# OLED.net
KiCad netlist of a schematic drawn in Altium Designer
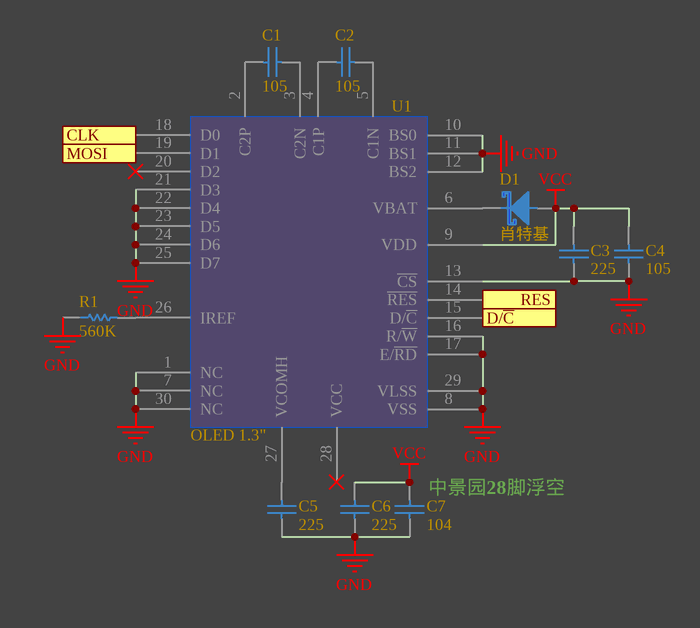
[diagram p0: OLED.SchDoc]

(export (version "E")
  (design (tool "Eeschema 10.0.6"))
  (components
    (comp (ref "C1")
      (value "105")
      (footprint "C0603")
      (description "Capacitor")
      (fields (field (name "PUBLISHER") "Altium Limited"))
      (libsource (lib "iMag") (part "电容"))
    )
    (comp (ref "C2")
      (value "105")
      (footprint "C0603")
      (description "Capacitor")
      (fields (field (name "PUBLISHER") "Altium Limited"))
      (libsource (lib "iMag") (part "电容"))
    )
    (comp (ref "C3")
      (value "225")
      (footprint "C0603")
      (description "Capacitor")
      (fields (field (name "PUBLISHER") "Altium Limited"))
      (libsource (lib "iMag") (part "电容"))
    )
    (comp (ref "C4")
      (value "105")
      (footprint "C0603")
      (description "Capacitor")
      (fields (field (name "PUBLISHER") "Altium Limited"))
      (libsource (lib "iMag") (part "电容"))
    )
    (comp (ref "C5")
      (value "225")
      (footprint "C0603")
      (description "Capacitor")
      (fields (field (name "PUBLISHER") "Altium Limited"))
      (libsource (lib "iMag") (part "电容"))
    )
    (comp (ref "C6")
      (value "225")
      (footprint "C0603")
      (description "Capacitor")
      (fields (field (name "PUBLISHER") "Altium Limited"))
      (libsource (lib "iMag") (part "电容"))
    )
    (comp (ref "C7")
      (value "104")
      (footprint "C0402")
      (description "Capacitor")
      (fields (field (name "PUBLISHER") "Altium Limited"))
      (libsource (lib "iMag") (part "电容"))
    )
    (comp (ref "D1")
      (value "肖特基")
      (footprint "SOD-123")
      (description "Schottky Diode")
      (libsource (lib "iMag") (part "肖特基"))
    )
    (comp (ref "R1")
      (value "560K")
      (footprint "R0402")
      (description "Resistor")
      (fields (field (name "PUBLISHER") "Altium Limited"))
      (libsource (lib "iMag") (part "电阻"))
    )
    (comp (ref "U1")
      (value "OLED 1.3\"")
      (footprint "OLED1.3\"")
      (description "SSD1306")
      (libsource (lib "iMag") (part "SSD1315"))
    )
  )
  (nets
    (net (code "1") (name "/CLK") (class "Default")
      (node (ref "U1") (pin "18") (pinfunction "D0_18") (pintype "passive"))
    )
    (net (code "2") (name "/D{slash}~{C}") (class "Default")
      (node (ref "U1") (pin "15") (pinfunction "D/~{C}_15") (pintype "passive"))
    )
    (net (code "3") (name "/MOSI") (class "Default")
      (node (ref "U1") (pin "19") (pinfunction "D1_19") (pintype "passive"))
    )
    (net (code "4") (name "/RES") (class "Default")
      (node (ref "U1") (pin "14") (pinfunction "RES_14") (pintype "passive"))
    )
    (net (code "5") (name "GND") (class "Default")
      (node (ref "C3") (pin "1") (pinfunction "1_1") (pintype "passive"))
      (node (ref "C4") (pin "1") (pinfunction "1_1") (pintype "passive"))
      (node (ref "C5") (pin "1") (pinfunction "1_1") (pintype "passive"))
      (node (ref "C6") (pin "1") (pinfunction "1_1") (pintype "passive"))
      (node (ref "C7") (pin "1") (pinfunction "1_1") (pintype "passive"))
      (node (ref "R1") (pin "1") (pinfunction "1_1") (pintype "passive"))
      (node (ref "U1") (pin "1") (pinfunction "NC_1") (pintype "passive"))
      (node (ref "U1") (pin "10") (pinfunction "BS0_10") (pintype "passive"))
      (node (ref "U1") (pin "11") (pinfunction "BS1_11") (pintype "passive"))
      (node (ref "U1") (pin "12") (pinfunction "BS2_12") (pintype "passive"))
      (node (ref "U1") (pin "13") (pinfunction "CS_13") (pintype "passive"))
      (node (ref "U1") (pin "16") (pinfunction "R/~{W}_16") (pintype "passive"))
      (node (ref "U1") (pin "17") (pinfunction "E/~{RD}_17") (pintype "passive"))
      (node (ref "U1") (pin "21") (pinfunction "D3_21") (pintype "passive"))
      (node (ref "U1") (pin "22") (pinfunction "D4_22") (pintype "passive"))
      (node (ref "U1") (pin "23") (pinfunction "D5_23") (pintype "passive"))
      (node (ref "U1") (pin "24") (pinfunction "D6_24") (pintype "passive"))
      (node (ref "U1") (pin "25") (pinfunction "D7_25") (pintype "passive"))
      (node (ref "U1") (pin "29") (pinfunction "VLSS_29") (pintype "passive"))
      (node (ref "U1") (pin "30") (pinfunction "NC_30") (pintype "passive"))
      (node (ref "U1") (pin "7") (pinfunction "NC_7") (pintype "passive"))
      (node (ref "U1") (pin "8") (pinfunction "VSS_8") (pintype "passive"))
    )
    (net (code "6") (name "Net-(D1-K)") (class "Default")
      (node (ref "D1") (pin "2") (pinfunction "K_2") (pintype "passive"))
      (node (ref "U1") (pin "6") (pinfunction "VBAT_6") (pintype "passive"))
    )
    (net (code "7") (name "Net-(U1-C1N)") (class "Default")
      (node (ref "C2") (pin "2") (pinfunction "2_2") (pintype "passive"))
      (node (ref "U1") (pin "5") (pinfunction "C1N_5") (pintype "passive"))
    )
    (net (code "8") (name "Net-(U1-C1P)") (class "Default")
      (node (ref "C2") (pin "1") (pinfunction "1_1") (pintype "passive"))
      (node (ref "U1") (pin "4") (pinfunction "C1P_4") (pintype "passive"))
    )
    (net (code "9") (name "Net-(U1-C2N)") (class "Default")
      (node (ref "C1") (pin "2") (pinfunction "2_2") (pintype "passive"))
      (node (ref "U1") (pin "3") (pinfunction "C2N_3") (pintype "passive"))
    )
    (net (code "10") (name "Net-(U1-C2P)") (class "Default")
      (node (ref "C1") (pin "1") (pinfunction "1_1") (pintype "passive"))
      (node (ref "U1") (pin "2") (pinfunction "C2P_2") (pintype "passive"))
    )
    (net (code "11") (name "Net-(U1-IREF)") (class "Default")
      (node (ref "R1") (pin "2") (pinfunction "2_2") (pintype "passive"))
      (node (ref "U1") (pin "26") (pinfunction "IREF_26") (pintype "passive"))
    )
    (net (code "12") (name "Net-(U1-VCOMH)") (class "Default")
      (node (ref "C5") (pin "2") (pinfunction "2_2") (pintype "passive"))
      (node (ref "U1") (pin "27") (pinfunction "VCOMH_27") (pintype "passive"))
    )
    (net (code "13") (name "VCC") (class "Default")
      (node (ref "C3") (pin "2") (pinfunction "2_2") (pintype "passive"))
      (node (ref "C4") (pin "2") (pinfunction "2_2") (pintype "passive"))
      (node (ref "C6") (pin "2") (pinfunction "2_2") (pintype "passive"))
      (node (ref "C7") (pin "2") (pinfunction "2_2") (pintype "passive"))
      (node (ref "D1") (pin "1") (pinfunction "A_1") (pintype "passive"))
      (node (ref "U1") (pin "9") (pinfunction "VDD_9") (pintype "passive"))
    )
    (net (code "14") (name "unconnected-(U1-D2-Pad20)") (class "Default")
      (node (ref "U1") (pin "20") (pinfunction "D2_20") (pintype "passive+no_connect"))
    )
    (net (code "15") (name "unconnected-(U1-VCC-Pad28)") (class "Default")
      (node (ref "U1") (pin "28") (pinfunction "VCC_28") (pintype "passive+no_connect"))
    )
  )
)
